# 2_PFC.net
KiCad netlist of a schematic drawn in Altium Designer
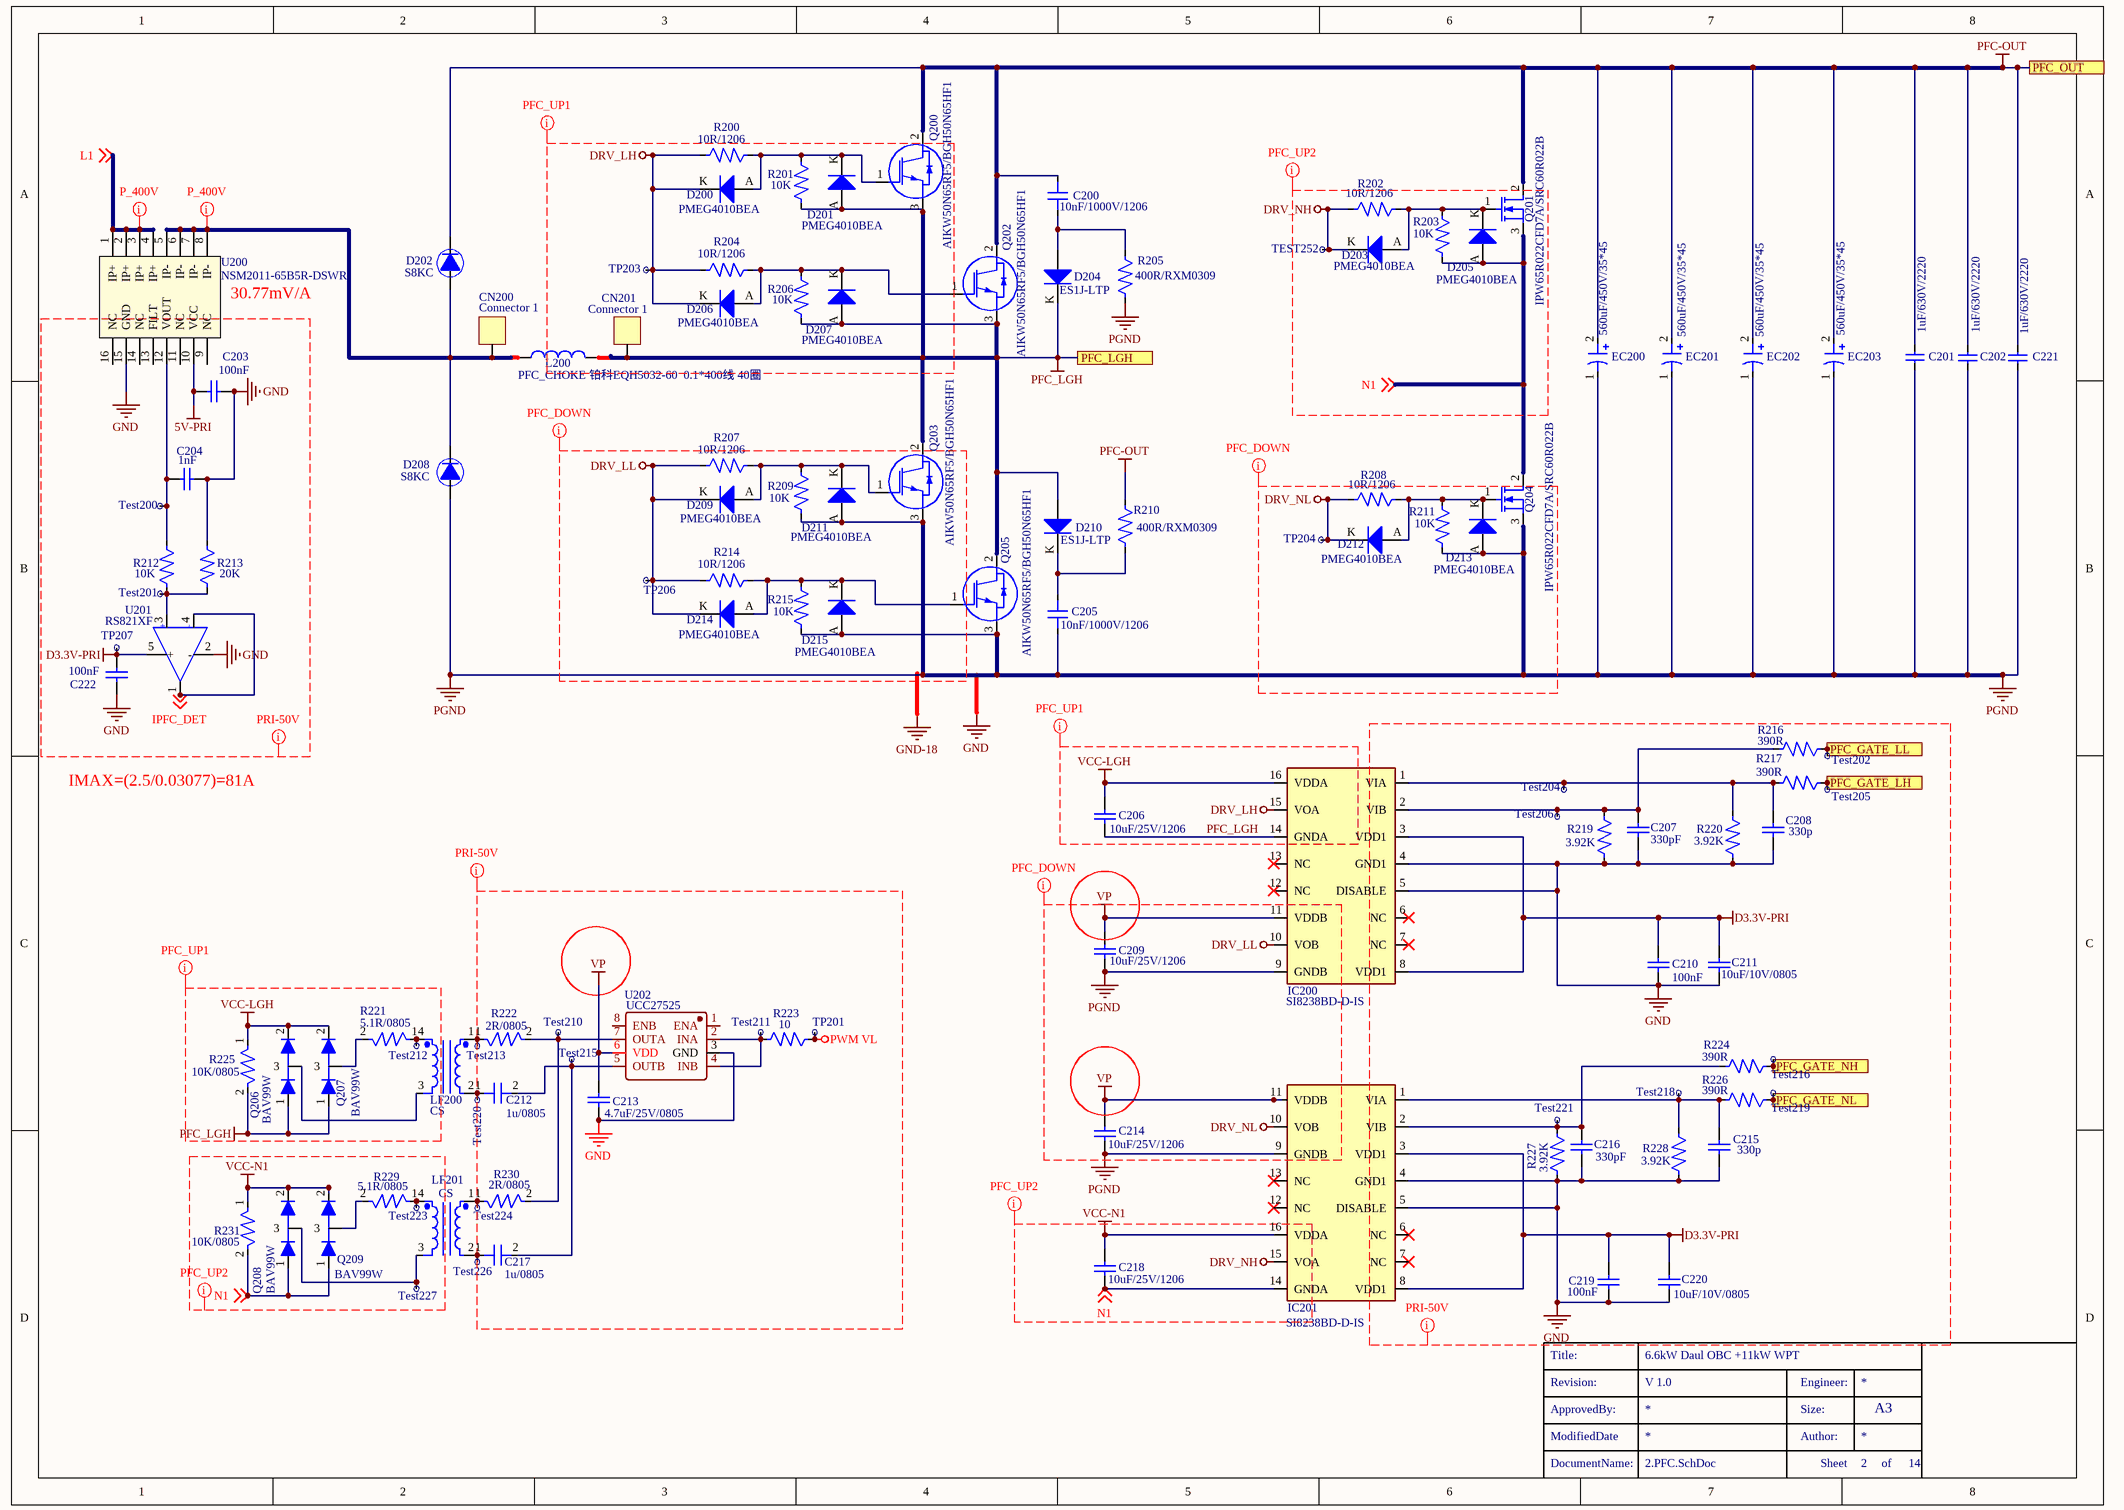
[diagram p0: 2.PFC.SchDoc]

(export (version "E")
  (design (tool "Eeschema 10.0.6"))
  (components
    (comp (ref "C200")
      (value "10nF/1000V/1206")
      (footprint "C1206")
      (description "MLCC Capacitor")
      (libsource (lib "GENERAL") (part "CAPACITOR_1206"))
    )
    (comp (ref "C201")
      (value "1uF/630V/2220")
      (footprint "C2220")
      (description "CBB21_105/630V")
      (libsource (lib "CAP_TH") (part "100033967"))
    )
    (comp (ref "C202")
      (value "1uF/630V/2220")
      (footprint "C2220")
      (description "CBB21_105/630V")
      (libsource (lib "CAP_TH") (part "100033967"))
    )
    (comp (ref "C203")
      (value "100nF")
      (footprint "C0402")
      (description "CAP")
      (libsource (lib "HUNENG") (part "CAP"))
    )
    (comp (ref "C204")
      (value "1nF")
      (footprint "C0402")
      (description "CAP")
      (libsource (lib "HUNENG") (part "CAP"))
    )
    (comp (ref "C205")
      (value "10nF/1000V/1206")
      (footprint "C1206")
      (description "MLCC Capacitor")
      (libsource (lib "GENERAL") (part "CAPACITOR_1206"))
    )
    (comp (ref "C206")
      (value "10uF/25V/1206")
      (footprint "C1206")
      (description "Capacitor")
      (fields (field (name "PUBLISHER") "Altium Limited"))
      (libsource (lib "*") (part "Cap"))
    )
    (comp (ref "C207")
      (value "330pF")
      (footprint "C0402")
      (description "CAP")
      (libsource (lib "HUNENG") (part "CAP"))
    )
    (comp (ref "C208")
      (value "330p")
      (footprint "C0402")
      (description "CAP")
      (libsource (lib "HUNENG") (part "CAP"))
    )
    (comp (ref "C209")
      (value "10uF/25V/1206")
      (footprint "C1206")
      (description "Capacitor")
      (fields (field (name "PUBLISHER") "Altium Limited"))
      (libsource (lib "*") (part "Cap"))
    )
    (comp (ref "C210")
      (value "100nF")
      (footprint "C0402")
      (description "CAP")
      (libsource (lib "HUNENG") (part "CAP"))
    )
    (comp (ref "C211")
      (value "10uF/10V/0805")
      (footprint "C0805")
      (description "CAP")
      (libsource (lib "HUNENG") (part "CAP"))
    )
    (comp (ref "C212")
      (value "1u/0805")
      (footprint "C0805")
      (description "CC0603KRX7R7BB105")
      (libsource (lib "GENERAL") (part "CAPACITOR_ YCAP"))
    )
    (comp (ref "C213")
      (value "4.7uF/25V/0805")
      (footprint "C0805")
      (description "Capacitor")
      (fields (field (name "PUBLISHER") "Altium Limited"))
      (libsource (lib "*") (part "Cap"))
    )
    (comp (ref "C214")
      (value "10uF/25V/1206")
      (footprint "C1206")
      (description "Capacitor")
      (fields (field (name "PUBLISHER") "Altium Limited"))
      (libsource (lib "*") (part "Cap"))
    )
    (comp (ref "C215")
      (value "330p")
      (footprint "C0402")
      (description "CAP")
      (libsource (lib "HUNENG") (part "CAP"))
    )
    (comp (ref "C216")
      (value "330pF")
      (footprint "C0402")
      (description "CAP")
      (libsource (lib "HUNENG") (part "CAP"))
    )
    (comp (ref "C217")
      (value "1u/0805")
      (footprint "C0805")
      (description "CC0603KRX7R7BB105")
      (libsource (lib "GENERAL") (part "CAPACITOR_ YCAP"))
    )
    (comp (ref "C218")
      (value "10uF/25V/1206")
      (footprint "C1206")
      (description "Capacitor")
      (fields (field (name "PUBLISHER") "Altium Limited"))
      (libsource (lib "*") (part "Cap"))
    )
    (comp (ref "C219")
      (value "100nF")
      (footprint "C0402")
      (description "CAP")
      (libsource (lib "HUNENG") (part "CAP"))
    )
    (comp (ref "C220")
      (value "10uF/10V/0805")
      (footprint "C0805")
      (description "CAP")
      (libsource (lib "HUNENG") (part "CAP"))
    )
    (comp (ref "C221")
      (value "1uF/630V/2220")
      (footprint "C2220")
      (description "CBB21_105/630V")
      (libsource (lib "CAP_TH") (part "100033967"))
    )
    (comp (ref "C222")
      (value "100nF")
      (footprint "C0402")
      (description "CAP")
      (libsource (lib "HUNENG") (part "CAP"))
    )
    (comp (ref "CN200")
      (value "Connector 1")
      (footprint "CON_4-7*5")
      (description "Header, 1-Pin")
      (fields (field (name "PUBLISHER") "Altium Limited"))
      (libsource (lib "PL Connectors") (part "Connector 1"))
    )
    (comp (ref "CN201")
      (value "Connector 1")
      (footprint "CON_4")
      (description "Header, 1-Pin")
      (fields (field (name "PUBLISHER") "Altium Limited"))
      (libsource (lib "PL Connectors") (part "Connector 1"))
    )
    (comp (ref "D200")
      (value "PMEG4010BEA")
      (footprint "D_SOD323")
      (description "30V 200mA SOD523 NXP")
      (libsource (lib "GENERAL") (part "DIODE_BAT54J"))
    )
    (comp (ref "D201")
      (value "PMEG4010BEA")
      (footprint "D_SOD323")
      (description "30V 200mA SOD523 NXP")
      (libsource (lib "GENERAL") (part "DIODE_BAT54J"))
    )
    (comp (ref "D202")
      (value "S8KC")
      (footprint "D_SMC")
      (description "800V 8A SMC LITEON")
      (libsource (lib "GENERAL") (part "DIODE_HIGH CURRENT_SMD"))
    )
    (comp (ref "D203")
      (value "PMEG4010BEA")
      (footprint "D_SOD323")
      (description "30V 200mA SOD523 NXP")
      (libsource (lib "GENERAL") (part "DIODE_BAT54J"))
    )
    (comp (ref "D204")
      (value "ES1J-LTP")
      (footprint "DO-214AC")
      (description "600V 1A DO-214AC MCC")
      (libsource (lib "GENERAL") (part "DIODE_MICRO"))
    )
    (comp (ref "D205")
      (value "PMEG4010BEA")
      (footprint "D_SOD323")
      (description "30V 200mA SOD523 NXP")
      (libsource (lib "GENERAL") (part "DIODE_BAT54J"))
    )
    (comp (ref "D206")
      (value "PMEG4010BEA")
      (footprint "D_SOD323")
      (description "30V 200mA SOD523 NXP")
      (libsource (lib "GENERAL") (part "DIODE_BAT54J"))
    )
    (comp (ref "D207")
      (value "PMEG4010BEA")
      (footprint "D_SOD323")
      (description "30V 200mA SOD523 NXP")
      (libsource (lib "GENERAL") (part "DIODE_BAT54J"))
    )
    (comp (ref "D208")
      (value "S8KC")
      (footprint "D_SMC")
      (description "800V 8A SMC LITEON")
      (libsource (lib "GENERAL") (part "DIODE_HIGH CURRENT_SMD"))
    )
    (comp (ref "D209")
      (value "PMEG4010BEA")
      (footprint "D_SOD323")
      (description "30V 200mA SOD523 NXP")
      (libsource (lib "GENERAL") (part "DIODE_BAT54J"))
    )
    (comp (ref "D210")
      (value "ES1J-LTP")
      (footprint "DO-214AC")
      (description "600V 1A DO-214AC MCC")
      (libsource (lib "GENERAL") (part "DIODE_MICRO"))
    )
    (comp (ref "D211")
      (value "PMEG4010BEA")
      (footprint "D_SOD323")
      (description "30V 200mA SOD523 NXP")
      (libsource (lib "GENERAL") (part "DIODE_BAT54J"))
    )
    (comp (ref "D212")
      (value "PMEG4010BEA")
      (footprint "D_SOD323")
      (description "30V 200mA SOD523 NXP")
      (libsource (lib "GENERAL") (part "DIODE_BAT54J"))
    )
    (comp (ref "D213")
      (value "PMEG4010BEA")
      (footprint "D_SOD323")
      (description "30V 200mA SOD523 NXP")
      (libsource (lib "GENERAL") (part "DIODE_BAT54J"))
    )
    (comp (ref "D214")
      (value "PMEG4010BEA")
      (footprint "D_SOD323")
      (description "30V 200mA SOD523 NXP")
      (libsource (lib "GENERAL") (part "DIODE_BAT54J"))
    )
    (comp (ref "D215")
      (value "PMEG4010BEA")
      (footprint "D_SOD323")
      (description "30V 200mA SOD523 NXP")
      (libsource (lib "GENERAL") (part "DIODE_BAT54J"))
    )
    (comp (ref "EC200")
      (value "560uF/450V/35*45")
      (footprint "Ecap_D35(e1)_H25")
      (description "560uF/450V 20% 35*45")
      (libsource (lib "中港电力原理图符号库(2.0)") (part "CAP_Ecap"))
    )
    (comp (ref "EC201")
      (value "560uF/450V/35*45")
      (footprint "Ecap_D35(e1)_H25")
      (description "560uF/450V 20% 35*45")
      (libsource (lib "中港电力原理图符号库(2.0)") (part "CAP_Ecap"))
    )
    (comp (ref "EC202")
      (value "560uF/450V/35*45")
      (footprint "Ecap_D35(e1)_H25")
      (description "560uF/450V 20% 35*45")
      (libsource (lib "中港电力原理图符号库(2.0)") (part "CAP_Ecap"))
    )
    (comp (ref "EC203")
      (value "560uF/450V/35*45")
      (footprint "Ecap_D35(e1)_H25")
      (description "560uF/450V 20% 35*45")
      (libsource (lib "中港电力原理图符号库(2.0)") (part "CAP_Ecap"))
    )
    (comp (ref "IC200")
      (value "SI8238BD‐D‐IS")
      (footprint "SOIC_W_16")
      (libsource (lib "") (part "ADuM4223/ADuM3223_1"))
    )
    (comp (ref "IC201")
      (value "SI8238BD‐D‐IS")
      (footprint "SOIC_W_16")
      (libsource (lib "HUNENG") (part "ADuM4223/ADuM3223"))
    )
    (comp (ref "L200")
      (value "PFC_CHOKE 铂科EQH5032-60  0.1*400线 40圈")
      (footprint "EQ5032-60 立式")
      (description "Inductor")
      (fields (field (name "PUBLISHER") "Altium Limited"))
      (libsource (lib "Miscellaneous Devices") (part "Inductor"))
    )
    (comp (ref "LF200")
      (value "CS")
      (footprint "GATE DRIVER EE5_0")
      (description "current transformer")
      (libsource (lib "原理图符号库2.0") (part "CS"))
    )
    (comp (ref "LF201")
      (value "CS")
      (footprint "GATE DRIVER EE5_0")
      (description "current transformer")
      (libsource (lib "原理图符号库2.0") (part "CS"))
    )
    (comp (ref "Q200")
      (value "AIKW50N65RF5/BGH50N65HF1")
      (footprint "Q_TO-247_TH _1")
      (libsource (lib "原理图符号库2.0") (part "TO-247-3"))
    )
    (comp (ref "Q201")
      (value "IPW65R022CFD7A/SRC60R022B")
      (footprint "Q_TO-247_TH _1")
      (description "N MOS FET")
      (libsource (lib "原理图符号库2.0") (part "MOSFET_N CHANNEL"))
    )
    (comp (ref "Q202")
      (value "AIKW50N65RF5/BGH50N65HF1")
      (footprint "Q_TO-247_TH _1")
      (libsource (lib "原理图符号库2.0") (part "TO-247-3"))
    )
    (comp (ref "Q203")
      (value "AIKW50N65RF5/BGH50N65HF1")
      (footprint "Q_TO-247_TH _1")
      (libsource (lib "原理图符号库2.0") (part "TO-247-3"))
    )
    (comp (ref "Q204")
      (value "IPW65R022CFD7A/SRC60R022B")
      (footprint "Q_TO-247_TH _1")
      (description "N MOS FET")
      (libsource (lib "原理图符号库2.0") (part "MOSFET_N CHANNEL"))
    )
    (comp (ref "Q205")
      (value "AIKW50N65RF5/BGH50N65HF1")
      (footprint "Q_TO-247_TH _1")
      (libsource (lib "原理图符号库2.0") (part "TO-247-3"))
    )
    (comp (ref "Q206") (value "BAV99W") (footprint "SOT323 - 2") (libsource (lib "原理图符号库2.0") (part "BAV99")))
    (comp (ref "Q207") (value "BAV99W") (footprint "SOT323 - 2") (libsource (lib "原理图符号库2.0") (part "BAV99")))
    (comp (ref "Q208") (value "BAV99W") (footprint "SOT323 - 2") (libsource (lib "原理图符号库2.0") (part "BAV99")))
    (comp (ref "Q209") (value "BAV99W") (footprint "SOT323 - 2") (libsource (lib "原理图符号库2.0") (part "BAV99")))
    (comp (ref "R200")
      (value "10R/1206")
      (footprint "R1206")
      (description "RESISTOR")
      (libsource (lib "GENERAL") (part "RESISTOR_0805"))
    )
    (comp (ref "R201")
      (value "10K")
      (footprint "R0402")
      (description "4.99K 1% 厚膜 1/16W 0402 YAGEO")
      (libsource (lib "GENERAL") (part "RESISTOR_0805"))
    )
    (comp (ref "R202")
      (value "10R/1206")
      (footprint "R1206")
      (description "RESISTOR")
      (libsource (lib "GENERAL") (part "RESISTOR_0805"))
    )
    (comp (ref "R203")
      (value "10K")
      (footprint "R0402")
      (description "4.99K 1% 厚膜 1/16W 0402 YAGEO")
      (libsource (lib "GENERAL") (part "RESISTOR_0805"))
    )
    (comp (ref "R204")
      (value "10R/1206")
      (footprint "R1206")
      (description "RESISTOR")
      (libsource (lib "GENERAL") (part "RESISTOR_0805"))
    )
    (comp (ref "R205")
      (value "400R/RXM0309")
      (footprint "RXM0309")
      (description "RESISTOR")
      (libsource (lib "GENERAL") (part "RESISTOR_1210"))
    )
    (comp (ref "R206")
      (value "10K")
      (footprint "R0402")
      (description "4.99K 1% 厚膜 1/16W 0402 YAGEO")
      (libsource (lib "GENERAL") (part "RESISTOR_0805"))
    )
    (comp (ref "R207")
      (value "10R/1206")
      (footprint "R1206")
      (description "RESISTOR")
      (libsource (lib "GENERAL") (part "RESISTOR_0805"))
    )
    (comp (ref "R208")
      (value "10R/1206")
      (footprint "R1206")
      (description "RESISTOR")
      (libsource (lib "GENERAL") (part "RESISTOR_0805"))
    )
    (comp (ref "R209")
      (value "10K")
      (footprint "R0402")
      (description "4.99K 1% 厚膜 1/16W 0402 YAGEO")
      (libsource (lib "GENERAL") (part "RESISTOR_0805"))
    )
    (comp (ref "R210")
      (value "400R/RXM0309")
      (footprint "RXM0309")
      (description "RESISTOR")
      (libsource (lib "GENERAL") (part "RESISTOR_1210"))
    )
    (comp (ref "R211")
      (value "10K")
      (footprint "R0402")
      (description "4.99K 1% 厚膜 1/16W 0402 YAGEO")
      (libsource (lib "GENERAL") (part "RESISTOR_0805"))
    )
    (comp (ref "R212")
      (value "10K")
      (footprint "R0402")
      (description "RESISTOR")
      (libsource (lib "HUNENG") (part "RESISTOR"))
    )
    (comp (ref "R213")
      (value "20K")
      (footprint "R0402")
      (description "RESISTOR")
      (libsource (lib "HUNENG") (part "RESISTOR"))
    )
    (comp (ref "R214")
      (value "10R/1206")
      (footprint "R1206")
      (description "RESISTOR")
      (libsource (lib "GENERAL") (part "RESISTOR_0805"))
    )
    (comp (ref "R215")
      (value "10K")
      (footprint "R0402")
      (description "4.99K 1% 厚膜 1/16W 0402 YAGEO")
      (libsource (lib "GENERAL") (part "RESISTOR_0805"))
    )
    (comp (ref "R216")
      (value "390R")
      (footprint "R0402")
      (description "RESISTOR")
      (libsource (lib "HUNENG") (part "RESISTOR"))
    )
    (comp (ref "R217")
      (value "390R")
      (footprint "R0402")
      (description "RESISTOR")
      (libsource (lib "HUNENG") (part "RESISTOR"))
    )
    (comp (ref "R219")
      (value "3.92K")
      (footprint "R0402")
      (description "RESISTOR")
      (libsource (lib "HUNENG") (part "RESISTOR"))
    )
    (comp (ref "R220")
      (value "3.92K")
      (footprint "R0402")
      (description "RESISTOR")
      (libsource (lib "HUNENG") (part "RESISTOR"))
    )
    (comp (ref "R221")
      (value "5.1R/0805")
      (footprint "R0805")
      (description "1206W4F0000T5E")
      (libsource (lib "GENERAL") (part "RESISTOR_1206"))
    )
    (comp (ref "R222")
      (value "2R/0805")
      (footprint "R0805")
      (description "1206W4F0000T5E")
      (libsource (lib "GENERAL") (part "RESISTOR_1206"))
    )
    (comp (ref "R223")
      (value "10")
      (footprint "R0402")
      (description "RESISTOR")
      (libsource (lib "中港电力原理图符号库(V1.3)") (part "RESISTOR"))
    )
    (comp (ref "R224")
      (value "390R")
      (footprint "R0402")
      (description "RESISTOR")
      (libsource (lib "HUNENG") (part "RESISTOR"))
    )
    (comp (ref "R225")
      (value "10K/0805")
      (footprint "R0805")
      (description "1206W4F0000T5E")
      (libsource (lib "GENERAL") (part "RESISTOR_1206"))
    )
    (comp (ref "R226")
      (value "390R")
      (footprint "R0402")
      (description "RESISTOR")
      (libsource (lib "HUNENG") (part "RESISTOR"))
    )
    (comp (ref "R227")
      (value "3.92K")
      (footprint "R0402")
      (description "RESISTOR")
      (libsource (lib "HUNENG") (part "RESISTOR"))
    )
    (comp (ref "R228")
      (value "3.92K")
      (footprint "R0402")
      (description "RESISTOR")
      (libsource (lib "HUNENG") (part "RESISTOR"))
    )
    (comp (ref "R229")
      (value "5.1R/0805")
      (footprint "R0805")
      (description "1206W4F0000T5E")
      (libsource (lib "GENERAL") (part "RESISTOR_1206"))
    )
    (comp (ref "R230")
      (value "2R/0805")
      (footprint "R0805")
      (description "1206W4F0000T5E")
      (libsource (lib "GENERAL") (part "RESISTOR_1206"))
    )
    (comp (ref "R231")
      (value "10K/0805")
      (footprint "R0805")
      (description "1206W4F0000T5E")
      (libsource (lib "GENERAL") (part "RESISTOR_1206"))
    )
    (comp (ref "Test200") (value "测试点") (footprint "测试点") (libsource (lib "") (part "测试点_1")))
    (comp (ref "Test201") (value "测试点") (footprint "测试点") (libsource (lib "") (part "测试点_1")))
    (comp (ref "Test202") (value "测试点") (footprint "测试点") (libsource (lib "") (part "测试点_1")))
    (comp (ref "Test204") (value "测试点") (footprint "测试点") (libsource (lib "") (part "测试点_1")))
    (comp (ref "Test205") (value "测试点") (footprint "测试点") (libsource (lib "") (part "测试点_1")))
    (comp (ref "Test206") (value "测试点") (footprint "测试点") (libsource (lib "") (part "测试点_1")))
    (comp (ref "Test210") (value "测试点") (footprint "测试点") (libsource (lib "原理图符号库2.0") (part "测试点")))
    (comp (ref "Test211") (value "测试点") (footprint "测试点") (libsource (lib "原理图符号库2.0") (part "测试点")))
    (comp (ref "Test212") (value "测试点") (footprint "测试点") (libsource (lib "原理图符号库2.0") (part "测试点")))
    (comp (ref "Test213") (value "测试点") (footprint "测试点") (libsource (lib "原理图符号库2.0") (part "测试点")))
    (comp (ref "Test215") (value "测试点") (footprint "测试点") (libsource (lib "原理图符号库2.0") (part "测试点")))
    (comp (ref "Test216") (value "测试点") (footprint "测试点") (libsource (lib "") (part "测试点_1")))
    (comp (ref "Test218") (value "测试点") (footprint "测试点") (libsource (lib "") (part "测试点_1")))
    (comp (ref "Test219") (value "测试点") (footprint "测试点") (libsource (lib "") (part "测试点_1")))
    (comp (ref "Test220") (value "测试点") (footprint "测试点") (libsource (lib "原理图符号库2.0") (part "测试点")))
    (comp (ref "Test221") (value "测试点") (footprint "测试点") (libsource (lib "") (part "测试点_1")))
    (comp (ref "Test223") (value "测试点") (footprint "测试点") (libsource (lib "原理图符号库2.0") (part "测试点")))
    (comp (ref "Test224") (value "测试点") (footprint "测试点") (libsource (lib "原理图符号库2.0") (part "测试点")))
    (comp (ref "Test226") (value "测试点") (footprint "测试点") (libsource (lib "原理图符号库2.0") (part "测试点")))
    (comp (ref "Test227") (value "测试点") (footprint "测试点") (libsource (lib "原理图符号库2.0") (part "测试点")))
    (comp (ref "TEST252") (value "测试点") (footprint "测试点") (libsource (lib "") (part "测试点_1")))
    (comp (ref "TP201") (value "测试点") (footprint "测试点") (libsource (lib "") (part "测试点_1")))
    (comp (ref "TP203") (value "测试点") (footprint "测试点") (libsource (lib "") (part "测试点_1")))
    (comp (ref "TP204") (value "测试点") (footprint "测试点") (libsource (lib "") (part "测试点_1")))
    (comp (ref "TP206") (value "测试点") (footprint "测试点") (libsource (lib "") (part "测试点_1")))
    (comp (ref "TP207") (value "测试点") (footprint "测试点") (libsource (lib "") (part "测试点_1")))
    (comp (ref "U200")
      (value "NSM2011-65B5R-DSWR")
      (footprint "SOIC_W_16")
      (libsource (lib "CUK-EV") (part "U-NSM2011-100B5R"))
    )
    (comp (ref "U201") (value "RS821XF") (footprint "SOT23-5") (libsource (lib "户能)") (part "OPA365")))
    (comp (ref "U202")
      (value "UCC27525")
      (footprint "SOIC_8")
      (fields
        (field (name "BOM_SUPPLIER PART") "C2690325")
        (field (name "BOM_MANUFACTURER PART") "SL27524")
        (field (name "CONTRIBUTOR") "LCSC")
      )
      (libsource (lib "SL27524") (part "SL27524"))
    )
  )
  (nets
    (net (code "1") (name "/PFC_GATE_LH") (class "Default")
      (node (ref "R217") (pin "1") (pinfunction "1_1") (pintype "passive"))
      (node (ref "Test205") (pin "1") (pinfunction "1_1") (pintype "passive"))
    )
    (net (code "2") (name "/PFC_GATE_LL") (class "Default")
      (node (ref "R216") (pin "1") (pinfunction "1_1") (pintype "passive"))
      (node (ref "Test202") (pin "1") (pinfunction "1_1") (pintype "passive"))
    )
    (net (code "3") (name "/PFC_GATE_NH") (class "Default")
      (node (ref "R224") (pin "1") (pinfunction "1_1") (pintype "passive"))
      (node (ref "Test216") (pin "1") (pinfunction "1_1") (pintype "passive"))
    )
    (net (code "4") (name "/PFC_GATE_NL") (class "Default")
      (node (ref "R226") (pin "1") (pinfunction "1_1") (pintype "passive"))
      (node (ref "Test219") (pin "1") (pinfunction "1_1") (pintype "passive"))
    )
    (net (code "5") (name "5V-PRI") (class "Default")
      (node (ref "C203") (pin "2") (pinfunction "2_2") (pintype "passive"))
      (node (ref "U200") (pin "10") (pinfunction "VCC_10") (pintype "passive"))
    )
    (net (code "6") (name "D3.3V-PRI") (class "Default")
      (node (ref "C210") (pin "2") (pinfunction "2_2") (pintype "passive"))
      (node (ref "C211") (pin "1") (pinfunction "1_1") (pintype "passive"))
      (node (ref "C219") (pin "2") (pinfunction "2_2") (pintype "passive"))
      (node (ref "C220") (pin "1") (pinfunction "1_1") (pintype "passive"))
      (node (ref "C222") (pin "1") (pinfunction "1_1") (pintype "passive"))
      (node (ref "IC200") (pin "3") (pinfunction "VDD1_3") (pintype "passive"))
      (node (ref "IC200") (pin "8") (pinfunction "VDD1_8") (pintype "passive"))
      (node (ref "IC201") (pin "3") (pinfunction "VDD1_3") (pintype "passive"))
      (node (ref "IC201") (pin "8") (pinfunction "VDD1_8") (pintype "passive"))
      (node (ref "TP207") (pin "1") (pinfunction "1_1") (pintype "passive"))
      (node (ref "U201") (pin "5") (pinfunction "+_5") (pintype "passive"))
    )
    (net (code "7") (name "DRV_LH") (class "Default")
      (node (ref "D200") (pin "K") (pinfunction "K_K") (pintype "passive"))
      (node (ref "D206") (pin "K") (pinfunction "K_K") (pintype "passive"))
      (node (ref "IC200") (pin "15") (pinfunction "VOA_15") (pintype "passive"))
      (node (ref "R200") (pin "2") (pinfunction "2_2") (pintype "passive"))
      (node (ref "R204") (pin "2") (pinfunction "2_2") (pintype "passive"))
      (node (ref "TP203") (pin "1") (pinfunction "1_1") (pintype "passive"))
    )
    (net (code "8") (name "DRV_LL") (class "Default")
      (node (ref "D209") (pin "K") (pinfunction "K_K") (pintype "passive"))
      (node (ref "D214") (pin "K") (pinfunction "K_K") (pintype "passive"))
      (node (ref "IC200") (pin "10") (pinfunction "VOB_10") (pintype "passive"))
      (node (ref "R207") (pin "2") (pinfunction "2_2") (pintype "passive"))
      (node (ref "R214") (pin "2") (pinfunction "2_2") (pintype "passive"))
      (node (ref "TP206") (pin "1") (pinfunction "1_1") (pintype "passive"))
    )
    (net (code "9") (name "DRV_NH") (class "Default")
      (node (ref "D203") (pin "K") (pinfunction "K_K") (pintype "passive"))
      (node (ref "IC201") (pin "15") (pinfunction "VOA_15") (pintype "passive"))
      (node (ref "R202") (pin "2") (pinfunction "2_2") (pintype "passive"))
      (node (ref "TEST252") (pin "1") (pinfunction "1_1") (pintype "passive"))
    )
    (net (code "10") (name "DRV_NL") (class "Default")
      (node (ref "D212") (pin "K") (pinfunction "K_K") (pintype "passive"))
      (node (ref "IC201") (pin "10") (pinfunction "VOB_10") (pintype "passive"))
      (node (ref "R208") (pin "2") (pinfunction "2_2") (pintype "passive"))
      (node (ref "TP204") (pin "1") (pinfunction "1_1") (pintype "passive"))
    )
    (net (code "11") (name "GND") (class "Default")
      (node (ref "C203") (pin "1") (pinfunction "1_1") (pintype "passive"))
      (node (ref "C204") (pin "2") (pinfunction "2_2") (pintype "passive"))
      (node (ref "C207") (pin "1") (pinfunction "1_1") (pintype "passive"))
      (node (ref "C208") (pin "1") (pinfunction "1_1") (pintype "passive"))
      (node (ref "C210") (pin "1") (pinfunction "1_1") (pintype "passive"))
      (node (ref "C211") (pin "2") (pinfunction "2_2") (pintype "passive"))
      (node (ref "C213") (pin "1") (pinfunction "1_1") (pintype "passive"))
      (node (ref "C215") (pin "1") (pinfunction "1_1") (pintype "passive"))
      (node (ref "C216") (pin "1") (pinfunction "1_1") (pintype "passive"))
      (node (ref "C219") (pin "1") (pinfunction "1_1") (pintype "passive"))
      (node (ref "C220") (pin "2") (pinfunction "2_2") (pintype "passive"))
      (node (ref "C222") (pin "2") (pinfunction "2_2") (pintype "passive"))
      (node (ref "IC200") (pin "4") (pinfunction "GND1_4") (pintype "passive"))
      (node (ref "IC200") (pin "5") (pinfunction "DISABLE_5") (pintype "passive"))
      (node (ref "IC201") (pin "4") (pinfunction "GND1_4") (pintype "passive"))
      (node (ref "IC201") (pin "5") (pinfunction "DISABLE_5") (pintype "passive"))
      (node (ref "R213") (pin "2") (pinfunction "2_2") (pintype "passive"))
      (node (ref "R219") (pin "2") (pinfunction "2_2") (pintype "passive"))
      (node (ref "R220") (pin "2") (pinfunction "2_2") (pintype "passive"))
      (node (ref "R227") (pin "2") (pinfunction "2_2") (pintype "passive"))
      (node (ref "R228") (pin "2") (pinfunction "2_2") (pintype "passive"))
      (node (ref "U200") (pin "15") (pinfunction "GND_15") (pintype "passive"))
      (node (ref "U201") (pin "2") (pinfunction "-_2") (pintype "passive"))
      (node (ref "U202") (pin "3") (pinfunction "GND_3") (pintype "passive"))
    )
    (net (code "13") (name "IPFC_DET") (class "Default")
      (node (ref "U201") (pin "1") (pinfunction "OUTPUT_1") (pintype "passive"))
      (node (ref "U201") (pin "4") (pinfunction "-VIN_4") (pintype "passive"))
    )
    (net (code "14") (name "L1") (class "Default")
      (node (ref "U200") (pin "1") (pinfunction "IP+_1") (pintype "passive"))
      (node (ref "U200") (pin "2") (pinfunction "IP+_2") (pintype "passive"))
      (node (ref "U200") (pin "3") (pinfunction "IP+_3") (pintype "passive"))
      (node (ref "U200") (pin "4") (pinfunction "IP+_4") (pintype "passive"))
    )
    (net (code "15") (name "N1") (class "Default")
      (node (ref "C218") (pin "1") (pinfunction "1_1") (pintype "passive"))
      (node (ref "D205") (pin "A") (pinfunction "A_A") (pintype "passive"))
      (node (ref "IC201") (pin "14") (pinfunction "GNDA_14") (pintype "passive"))
      (node (ref "Q201") (pin "3") (pinfunction "S_3") (pintype "passive"))
      (node (ref "Q204") (pin "2") (pinfunction "D_2") (pintype "passive"))
      (node (ref "Q208") (pin "1") (pinfunction "A_1") (pintype "passive"))
      (node (ref "Q209") (pin "1") (pinfunction "A_1") (pintype "passive"))
      (node (ref "R203") (pin "2") (pinfunction "2_2") (pintype "passive"))
      (node (ref "R231") (pin "2") (pinfunction "2_2") (pintype "passive"))
    )
    (net (code "16") (name "Net-(C200-Pad2)") (class "Default")
      (node (ref "C200") (pin "2") (pinfunction "2_2") (pintype "passive"))
      (node (ref "D204") (pin "A") (pinfunction "A_A") (pintype "passive"))
      (node (ref "R205") (pin "1") (pinfunction "1_1") (pintype "passive"))
    )
    (net (code "17") (name "Net-(C205-Pad1)") (class "Default")
      (node (ref "C205") (pin "1") (pinfunction "1_1") (pintype "passive"))
      (node (ref "D210") (pin "K") (pinfunction "K_K") (pintype "passive"))
      (node (ref "R210") (pin "1") (pinfunction "1_1") (pintype "passive"))
    )
    (net (code "18") (name "Net-(C212-Pad1)") (class "Default")
      (node (ref "C212") (pin "1") (pinfunction "1_1") (pintype "passive"))
      (node (ref "LF200") (pin "2") (pintype "passive"))
      (node (ref "Test220") (pin "1") (pinfunction "1_1") (pintype "passive"))
    )
    (net (code "19") (name "Net-(C217-Pad1)") (class "Default")
      (node (ref "C217") (pin "1") (pinfunction "1_1") (pintype "passive"))
      (node (ref "LF201") (pin "2") (pintype "passive"))
      (node (ref "Test226") (pin "1") (pinfunction "1_1") (pintype "passive"))
    )
    (net (code "20") (name "Net-(CN200-Pad1)") (class "Default")
      (node (ref "CN200") (pin "1") (pinfunction "1_1") (pintype "passive"))
      (node (ref "D202") (pin "A") (pinfunction "A_A") (pintype "passive"))
      (node (ref "D208") (pin "K") (pinfunction "K_K") (pintype "passive"))
      (node (ref "U200") (pin "5") (pinfunction "IP-_5") (pintype "passive"))
      (node (ref "U200") (pin "6") (pinfunction "IP-_6") (pintype "passive"))
      (node (ref "U200") (pin "7") (pinfunction "IP-_7") (pintype "passive"))
      (node (ref "U200") (pin "8") (pinfunction "IP-_8") (pintype "passive"))
    )
    (net (code "21") (name "Net-(D200-PadA)") (class "Default")
      (node (ref "D200") (pin "A") (pinfunction "A_A") (pintype "passive"))
      (node (ref "D201") (pin "K") (pinfunction "K_K") (pintype "passive"))
      (node (ref "Q200") (pin "1") (pinfunction "1_1") (pintype "passive"))
      (node (ref "R200") (pin "1") (pinfunction "1_1") (pintype "passive"))
      (node (ref "R201") (pin "1") (pinfunction "1_1") (pintype "passive"))
    )
    (net (code "22") (name "Net-(D206-PadA)") (class "Default")
      (node (ref "D206") (pin "A") (pinfunction "A_A") (pintype "passive"))
      (node (ref "D207") (pin "K") (pinfunction "K_K") (pintype "passive"))
      (node (ref "Q202") (pin "1") (pinfunction "1_1") (pintype "passive"))
      (node (ref "R204") (pin "1") (pinfunction "1_1") (pintype "passive"))
      (node (ref "R206") (pin "1") (pinfunction "1_1") (pintype "passive"))
    )
    (net (code "23") (name "Net-(D209-PadA)") (class "Default")
      (node (ref "D209") (pin "A") (pinfunction "A_A") (pintype "passive"))
      (node (ref "D211") (pin "K") (pinfunction "K_K") (pintype "passive"))
      (node (ref "Q203") (pin "1") (pinfunction "1_1") (pintype "passive"))
      (node (ref "R207") (pin "1") (pinfunction "1_1") (pintype "passive"))
      (node (ref "R209") (pin "1") (pinfunction "1_1") (pintype "passive"))
    )
    (net (code "24") (name "Net-(D214-PadA)") (class "Default")
      (node (ref "D214") (pin "A") (pinfunction "A_A") (pintype "passive"))
      (node (ref "D215") (pin "K") (pinfunction "K_K") (pintype "passive"))
      (node (ref "Q205") (pin "1") (pinfunction "1_1") (pintype "passive"))
      (node (ref "R214") (pin "1") (pinfunction "1_1") (pintype "passive"))
      (node (ref "R215") (pin "1") (pinfunction "1_1") (pintype "passive"))
    )
    (net (code "25") (name "Net-(IC200-VIA)") (class "Default")
      (node (ref "C208") (pin "2") (pinfunction "2_2") (pintype "passive"))
      (node (ref "IC200") (pin "1") (pinfunction "VIA_1") (pintype "passive"))
      (node (ref "R217") (pin "2") (pinfunction "2_2") (pintype "passive"))
      (node (ref "R220") (pin "1") (pinfunction "1_1") (pintype "passive"))
      (node (ref "Test204") (pin "1") (pinfunction "1_1") (pintype "passive"))
    )
    (net (code "26") (name "Net-(IC200-VIB)") (class "Default")
      (node (ref "C207") (pin "2") (pinfunction "2_2") (pintype "passive"))
      (node (ref "IC200") (pin "2") (pinfunction "VIB_2") (pintype "passive"))
      (node (ref "R216") (pin "2") (pinfunction "2_2") (pintype "passive"))
      (node (ref "R219") (pin "1") (pinfunction "1_1") (pintype "passive"))
      (node (ref "Test206") (pin "1") (pinfunction "1_1") (pintype "passive"))
    )
    (net (code "27") (name "Net-(IC201-VIA)") (class "Default")
      (node (ref "C215") (pin "2") (pinfunction "2_2") (pintype "passive"))
      (node (ref "IC201") (pin "1") (pinfunction "VIA_1") (pintype "passive"))
      (node (ref "R226") (pin "2") (pinfunction "2_2") (pintype "passive"))
      (node (ref "R228") (pin "1") (pinfunction "1_1") (pintype "passive"))
      (node (ref "Test218") (pin "1") (pinfunction "1_1") (pintype "passive"))
    )
    (net (code "28") (name "Net-(IC201-VIB)") (class "Default")
      (node (ref "C216") (pin "2") (pinfunction "2_2") (pintype "passive"))
      (node (ref "IC201") (pin "2") (pinfunction "VIB_2") (pintype "passive"))
      (node (ref "R224") (pin "2") (pinfunction "2_2") (pintype "passive"))
      (node (ref "R227") (pin "1") (pinfunction "1_1") (pintype "passive"))
      (node (ref "Test221") (pin "1") (pinfunction "1_1") (pintype "passive"))
    )
    (net (code "29") (name "Net-(LF200-Pad1)") (class "Default")
      (node (ref "LF200") (pin "1") (pintype "passive"))
      (node (ref "R222") (pin "1") (pinfunction "1_1") (pintype "passive"))
      (node (ref "Test213") (pin "1") (pinfunction "1_1") (pintype "passive"))
    )
    (net (code "30") (name "Net-(LF200-Pad3)") (class "Default")
      (node (ref "LF200") (pin "3") (pintype "passive"))
      (node (ref "Q206") (pin "3") (pinfunction "3_3") (pintype "passive"))
    )
    (net (code "31") (name "Net-(LF200-Pad4)") (class "Default")
      (node (ref "LF200") (pin "4") (pintype "passive"))
      (node (ref "R221") (pin "1") (pinfunction "1_1") (pintype "passive"))
      (node (ref "Test212") (pin "1") (pinfunction "1_1") (pintype "passive"))
    )
    (net (code "32") (name "Net-(LF201-Pad1)") (class "Default")
      (node (ref "LF201") (pin "1") (pintype "passive"))
      (node (ref "R230") (pin "1") (pinfunction "1_1") (pintype "passive"))
      (node (ref "Test224") (pin "1") (pinfunction "1_1") (pintype "passive"))
    )
    (net (code "33") (name "Net-(LF201-Pad3)") (class "Default")
      (node (ref "LF201") (pin "3") (pintype "passive"))
      (node (ref "Q208") (pin "3") (pinfunction "3_3") (pintype "passive"))
      (node (ref "Test227") (pin "1") (pinfunction "1_1") (pintype "passive"))
    )
    (net (code "34") (name "Net-(LF201-Pad4)") (class "Default")
      (node (ref "LF201") (pin "4") (pintype "passive"))
      (node (ref "R229") (pin "1") (pinfunction "1_1") (pintype "passive"))
      (node (ref "Test223") (pin "1") (pinfunction "1_1") (pintype "passive"))
    )
    (net (code "35") (name "Net-(Q201-G)") (class "Default")
      (node (ref "D203") (pin "A") (pinfunction "A_A") (pintype "passive"))
      (node (ref "D205") (pin "K") (pinfunction "K_K") (pintype "passive"))
      (node (ref "Q201") (pin "1") (pinfunction "G_1") (pintype "passive"))
      (node (ref "R202") (pin "1") (pinfunction "1_1") (pintype "passive"))
      (node (ref "R203") (pin "1") (pinfunction "1_1") (pintype "passive"))
    )
    (net (code "36") (name "Net-(Q204-G)") (class "Default")
      (node (ref "D212") (pin "A") (pinfunction "A_A") (pintype "passive"))
      (node (ref "D213") (pin "K") (pinfunction "K_K") (pintype "passive"))
      (node (ref "Q204") (pin "1") (pinfunction "G_1") (pintype "passive"))
      (node (ref "R208") (pin "1") (pinfunction "1_1") (pintype "passive"))
      (node (ref "R211") (pin "1") (pinfunction "1_1") (pintype "passive"))
    )
    (net (code "37") (name "Net-(Q207-Pad3)") (class "Default")
      (node (ref "Q207") (pin "3") (pinfunction "3_3") (pintype "passive"))
      (node (ref "R221") (pin "2") (pinfunction "2_2") (pintype "passive"))
    )
    (net (code "38") (name "Net-(Q209-Pad3)") (class "Default")
      (node (ref "Q209") (pin "3") (pinfunction "3_3") (pintype "passive"))
      (node (ref "R229") (pin "2") (pinfunction "2_2") (pintype "passive"))
    )
    (net (code "39") (name "Net-(U200-VOUT)") (class "Default")
      (node (ref "C204") (pin "1") (pinfunction "1_1") (pintype "passive"))
      (node (ref "R212") (pin "2") (pinfunction "2_2") (pintype "passive"))
      (node (ref "Test200") (pin "1") (pinfunction "1_1") (pintype "passive"))
      (node (ref "U200") (pin "12") (pinfunction "VOUT_12") (pintype "passive"))
    )
    (net (code "40") (name "Net-(U201-+VIN)") (class "Default")
      (node (ref "R212") (pin "1") (pinfunction "1_1") (pintype "passive"))
      (node (ref "R213") (pin "1") (pinfunction "1_1") (pintype "passive"))
      (node (ref "Test201") (pin "1") (pinfunction "1_1") (pintype "passive"))
      (node (ref "U201") (pin "3") (pinfunction "+VIN_3") (pintype "passive"))
    )
    (net (code "41") (name "Net-(U202-INA)") (class "Default")
      (node (ref "R223") (pin "2") (pinfunction "2_2") (pintype "passive"))
      (node (ref "Test211") (pin "1") (pinfunction "1_1") (pintype "passive"))
      (node (ref "U202") (pin "2") (pinfunction "INA_2") (pintype "passive"))
      (node (ref "U202") (pin "4") (pinfunction "INB_4") (pintype "passive"))
    )
    (net (code "42") (name "Net-(U202-OUTA)") (class "Default")
      (node (ref "R222") (pin "2") (pinfunction "2_2") (pintype "passive"))
      (node (ref "R230") (pin "2") (pinfunction "2_2") (pintype "passive"))
      (node (ref "Test210") (pin "1") (pinfunction "1_1") (pintype "passive"))
      (node (ref "U202") (pin "7") (pinfunction "OUTA_7") (pintype "passive"))
    )
    (net (code "43") (name "Net-(U202-OUTB)") (class "Default")
      (node (ref "C212") (pin "2") (pinfunction "2_2") (pintype "passive"))
      (node (ref "C217") (pin "2") (pinfunction "2_2") (pintype "passive"))
      (node (ref "Test215") (pin "1") (pinfunction "1_1") (pintype "passive"))
      (node (ref "U202") (pin "5") (pinfunction "OUTB_5") (pintype "passive"))
    )
    (net (code "44") (name "PFC-OUT") (class "Default")
      (node (ref "C200") (pin "1") (pinfunction "1_1") (pintype "passive"))
      (node (ref "C201") (pin "2") (pinfunction "2_2") (pintype "passive"))
      (node (ref "C202") (pin "2") (pinfunction "2_2") (pintype "passive"))
      (node (ref "C221") (pin "2") (pinfunction "2_2") (pintype "passive"))
      (node (ref "D202") (pin "K") (pinfunction "K_K") (pintype "passive"))
      (node (ref "EC200") (pin "2") (pinfunction "2_2") (pintype "passive"))
      (node (ref "EC201") (pin "2") (pinfunction "2_2") (pintype "passive"))
      (node (ref "EC202") (pin "2") (pinfunction "2_2") (pintype "passive"))
      (node (ref "EC203") (pin "2") (pinfunction "2_2") (pintype "passive"))
      (node (ref "Q200") (pin "2") (pinfunction "2_2") (pintype "passive"))
      (node (ref "Q201") (pin "2") (pinfunction "D_2") (pintype "passive"))
      (node (ref "Q202") (pin "2") (pinfunction "2_2") (pintype "passive"))
      (node (ref "R210") (pin "2") (pinfunction "2_2") (pintype "passive"))
    )
    (net (code "45") (name "PFC_LGH") (class "Default")
      (node (ref "C206") (pin "1") (pinfunction "1_1") (pintype "passive"))
      (node (ref "CN201") (pin "1") (pinfunction "1_1") (pintype "passive"))
      (node (ref "D201") (pin "A") (pinfunction "A_A") (pintype "passive"))
      (node (ref "D204") (pin "K") (pinfunction "K_K") (pintype "passive"))
      (node (ref "D207") (pin "A") (pinfunction "A_A") (pintype "passive"))
      (node (ref "D210") (pin "A") (pinfunction "A_A") (pintype "passive"))
      (node (ref "IC200") (pin "14") (pinfunction "GNDA_14") (pintype "passive"))
      (node (ref "Q200") (pin "3") (pinfunction "3_3") (pintype "passive"))
      (node (ref "Q202") (pin "3") (pinfunction "3_3") (pintype "passive"))
      (node (ref "Q203") (pin "2") (pinfunction "2_2") (pintype "passive"))
      (node (ref "Q205") (pin "2") (pinfunction "2_2") (pintype "passive"))
      (node (ref "Q206") (pin "1") (pinfunction "A_1") (pintype "passive"))
      (node (ref "Q207") (pin "1") (pinfunction "A_1") (pintype "passive"))
      (node (ref "R201") (pin "2") (pinfunction "2_2") (pintype "passive"))
      (node (ref "R206") (pin "2") (pinfunction "2_2") (pintype "passive"))
      (node (ref "R225") (pin "2") (pinfunction "2_2") (pintype "passive"))
    )
    (net (code "46") (name "PGND") (class "Default")
      (node (ref "C201") (pin "1") (pinfunction "1_1") (pintype "passive"))
      (node (ref "C202") (pin "1") (pinfunction "1_1") (pintype "passive"))
      (node (ref "C205") (pin "2") (pinfunction "2_2") (pintype "passive"))
      (node (ref "C209") (pin "1") (pinfunction "1_1") (pintype "passive"))
      (node (ref "C214") (pin "1") (pinfunction "1_1") (pintype "passive"))
      (node (ref "C221") (pin "1") (pinfunction "1_1") (pintype "passive"))
      (node (ref "D208") (pin "A") (pinfunction "A_A") (pintype "passive"))
      (node (ref "D211") (pin "A") (pinfunction "A_A") (pintype "passive"))
      (node (ref "D213") (pin "A") (pinfunction "A_A") (pintype "passive"))
      (node (ref "D215") (pin "A") (pinfunction "A_A") (pintype "passive"))
      (node (ref "EC200") (pin "1") (pinfunction "1_1") (pintype "passive"))
      (node (ref "EC201") (pin "1") (pinfunction "1_1") (pintype "passive"))
      (node (ref "EC202") (pin "1") (pinfunction "1_1") (pintype "passive"))
      (node (ref "EC203") (pin "1") (pinfunction "1_1") (pintype "passive"))
      (node (ref "IC200") (pin "9") (pinfunction "GNDB_9") (pintype "passive"))
      (node (ref "IC201") (pin "9") (pinfunction "GNDB_9") (pintype "passive"))
      (node (ref "Q203") (pin "3") (pinfunction "3_3") (pintype "passive"))
      (node (ref "Q204") (pin "3") (pinfunction "S_3") (pintype "passive"))
      (node (ref "Q205") (pin "3") (pinfunction "3_3") (pintype "passive"))
      (node (ref "R205") (pin "2") (pinfunction "2_2") (pintype "passive"))
      (node (ref "R209") (pin "2") (pinfunction "2_2") (pintype "passive"))
      (node (ref "R211") (pin "2") (pinfunction "2_2") (pintype "passive"))
      (node (ref "R215") (pin "2") (pinfunction "2_2") (pintype "passive"))
    )
    (net (code "47") (name "PWM VL") (class "Default")
      (node (ref "R223") (pin "1") (pinfunction "1_1") (pintype "passive"))
      (node (ref "TP201") (pin "1") (pinfunction "1_1") (pintype "passive"))
    )
    (net (code "48") (name "VCC-LGH") (class "Default")
      (node (ref "C206") (pin "2") (pinfunction "2_2") (pintype "passive"))
      (node (ref "IC200") (pin "16") (pinfunction "VDDA_16") (pintype "passive"))
      (node (ref "Q206") (pin "2") (pinfunction "K_2") (pintype "passive"))
      (node (ref "Q207") (pin "2") (pinfunction "K_2") (pintype "passive"))
      (node (ref "R225") (pin "1") (pinfunction "1_1") (pintype "passive"))
    )
    (net (code "49") (name "VCC-N1") (class "Default")
      (node (ref "C218") (pin "2") (pinfunction "2_2") (pintype "passive"))
      (node (ref "IC201") (pin "16") (pinfunction "VDDA_16") (pintype "passive"))
      (node (ref "Q208") (pin "2") (pinfunction "K_2") (pintype "passive"))
      (node (ref "Q209") (pin "2") (pinfunction "K_2") (pintype "passive"))
      (node (ref "R231") (pin "1") (pinfunction "1_1") (pintype "passive"))
    )
    (net (code "50") (name "VP") (class "Default")
      (node (ref "C209") (pin "2") (pinfunction "2_2") (pintype "passive"))
      (node (ref "C213") (pin "2") (pinfunction "2_2") (pintype "passive"))
      (node (ref "C214") (pin "2") (pinfunction "2_2") (pintype "passive"))
      (node (ref "IC200") (pin "11") (pinfunction "VDDB_11") (pintype "passive"))
      (node (ref "IC201") (pin "11") (pinfunction "VDDB_11") (pintype "passive"))
      (node (ref "U202") (pin "6") (pinfunction "VDD_6") (pintype "passive"))
    )
    (net (code "51") (name "unconnected-(IC200-NC-Pad6)") (class "Default")
      (node (ref "IC200") (pin "6") (pinfunction "NC_6") (pintype "passive+no_connect"))
    )
    (net (code "52") (name "unconnected-(IC200-NC-Pad7)") (class "Default")
      (node (ref "IC200") (pin "7") (pinfunction "NC_7") (pintype "passive+no_connect"))
    )
    (net (code "53") (name "unconnected-(IC200-NC-Pad12)") (class "Default")
      (node (ref "IC200") (pin "12") (pinfunction "NC_12") (pintype "passive+no_connect"))
    )
    (net (code "54") (name "unconnected-(IC200-NC-Pad13)") (class "Default")
      (node (ref "IC200") (pin "13") (pinfunction "NC_13") (pintype "passive+no_connect"))
    )
    (net (code "55") (name "unconnected-(IC201-NC-Pad6)") (class "Default")
      (node (ref "IC201") (pin "6") (pinfunction "NC_6") (pintype "passive+no_connect"))
    )
    (net (code "56") (name "unconnected-(IC201-NC-Pad7)") (class "Default")
      (node (ref "IC201") (pin "7") (pinfunction "NC_7") (pintype "passive+no_connect"))
    )
    (net (code "57") (name "unconnected-(IC201-NC-Pad12)") (class "Default")
      (node (ref "IC201") (pin "12") (pinfunction "NC_12") (pintype "passive+no_connect"))
    )
    (net (code "58") (name "unconnected-(IC201-NC-Pad13)") (class "Default")
      (node (ref "IC201") (pin "13") (pinfunction "NC_13") (pintype "passive+no_connect"))
    )
    (net (code "59") (name "unconnected-(L200-Pad1)") (class "Default")
      (node (ref "L200") (pin "1") (pinfunction "1_1") (pintype "passive"))
    )
    (net (code "60") (name "unconnected-(L200-Pad2)") (class "Default")
      (node (ref "L200") (pin "2") (pinfunction "2_2") (pintype "passive"))
    )
    (net (code "61") (name "unconnected-(U200-FILT-Pad13)") (class "Default")
      (node (ref "U200") (pin "13") (pinfunction "FILT_13") (pintype "passive"))
    )
    (net (code "62") (name "unconnected-(U200-NC-Pad9)") (class "Default")
      (node (ref "U200") (pin "9") (pinfunction "NC_9") (pintype "passive"))
    )
    (net (code "63") (name "unconnected-(U200-NC-Pad11)") (class "Default")
      (node (ref "U200") (pin "11") (pinfunction "NC_11") (pintype "passive"))
    )
    (net (code "64") (name "unconnected-(U200-NC-Pad14)") (class "Default")
      (node (ref "U200") (pin "14") (pinfunction "NC_14") (pintype "passive"))
    )
    (net (code "65") (name "unconnected-(U200-NC-Pad16)") (class "Default")
      (node (ref "U200") (pin "16") (pinfunction "NC_16") (pintype "passive"))
    )
    (net (code "66") (name "unconnected-(U202-ENA-Pad1)") (class "Default")
      (node (ref "U202") (pin "1") (pinfunction "ENA_1") (pintype "passive"))
    )
    (net (code "67") (name "unconnected-(U202-ENB-Pad8)") (class "Default")
      (node (ref "U202") (pin "8") (pinfunction "ENB_8") (pintype "passive"))
    )
  )
)
